# Interconnect_board_v1p10.net
KiCad netlist of a schematic drawn in EAGLE
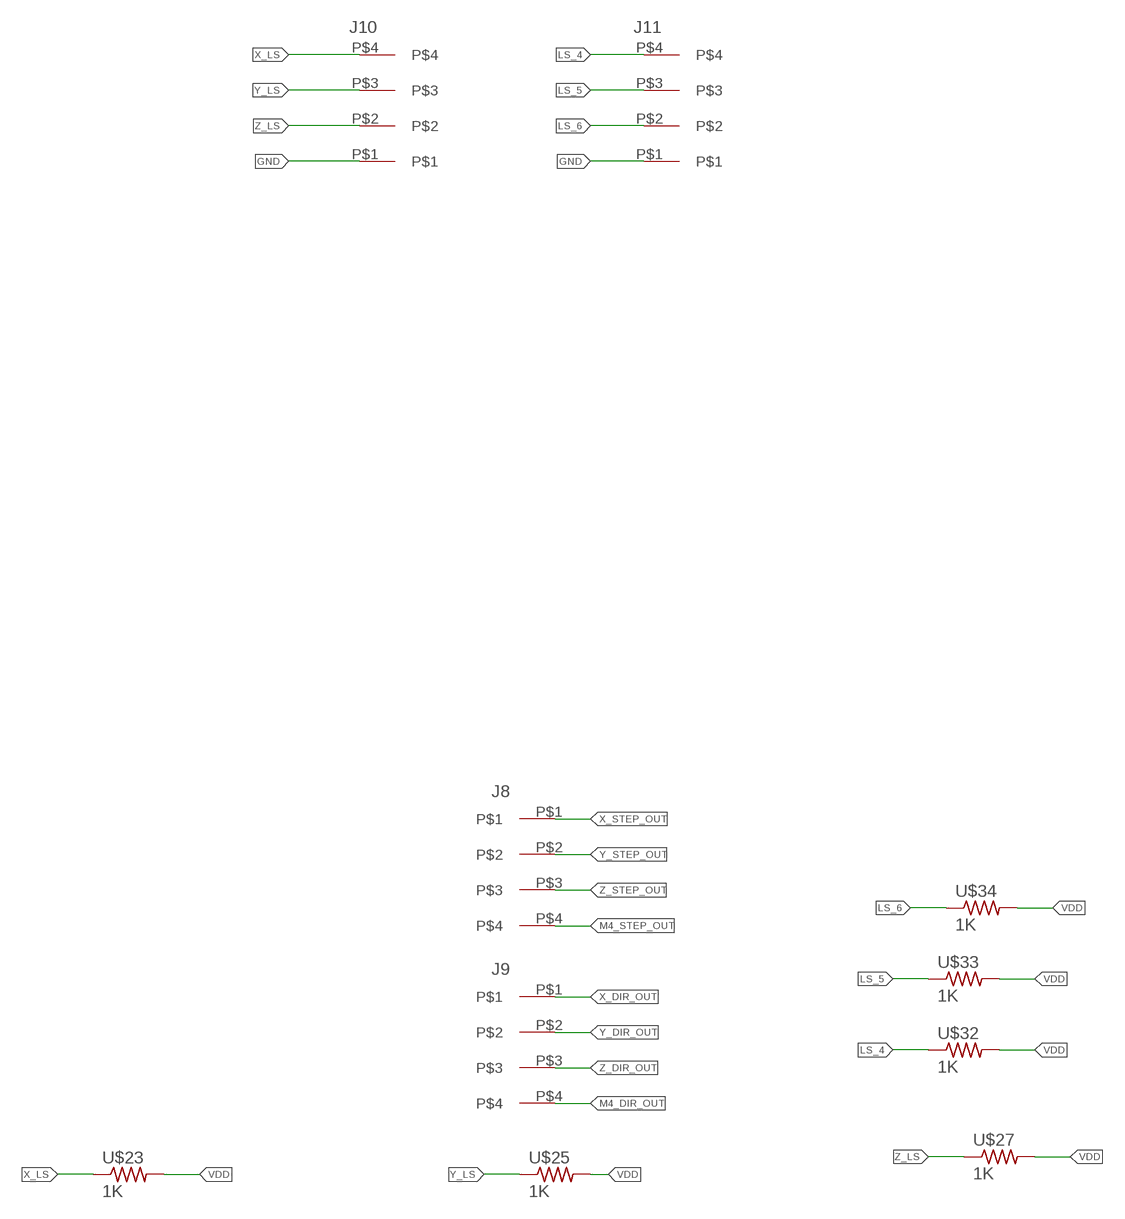
[diagram p0: schematic, sheet 1, part 1 of 2]
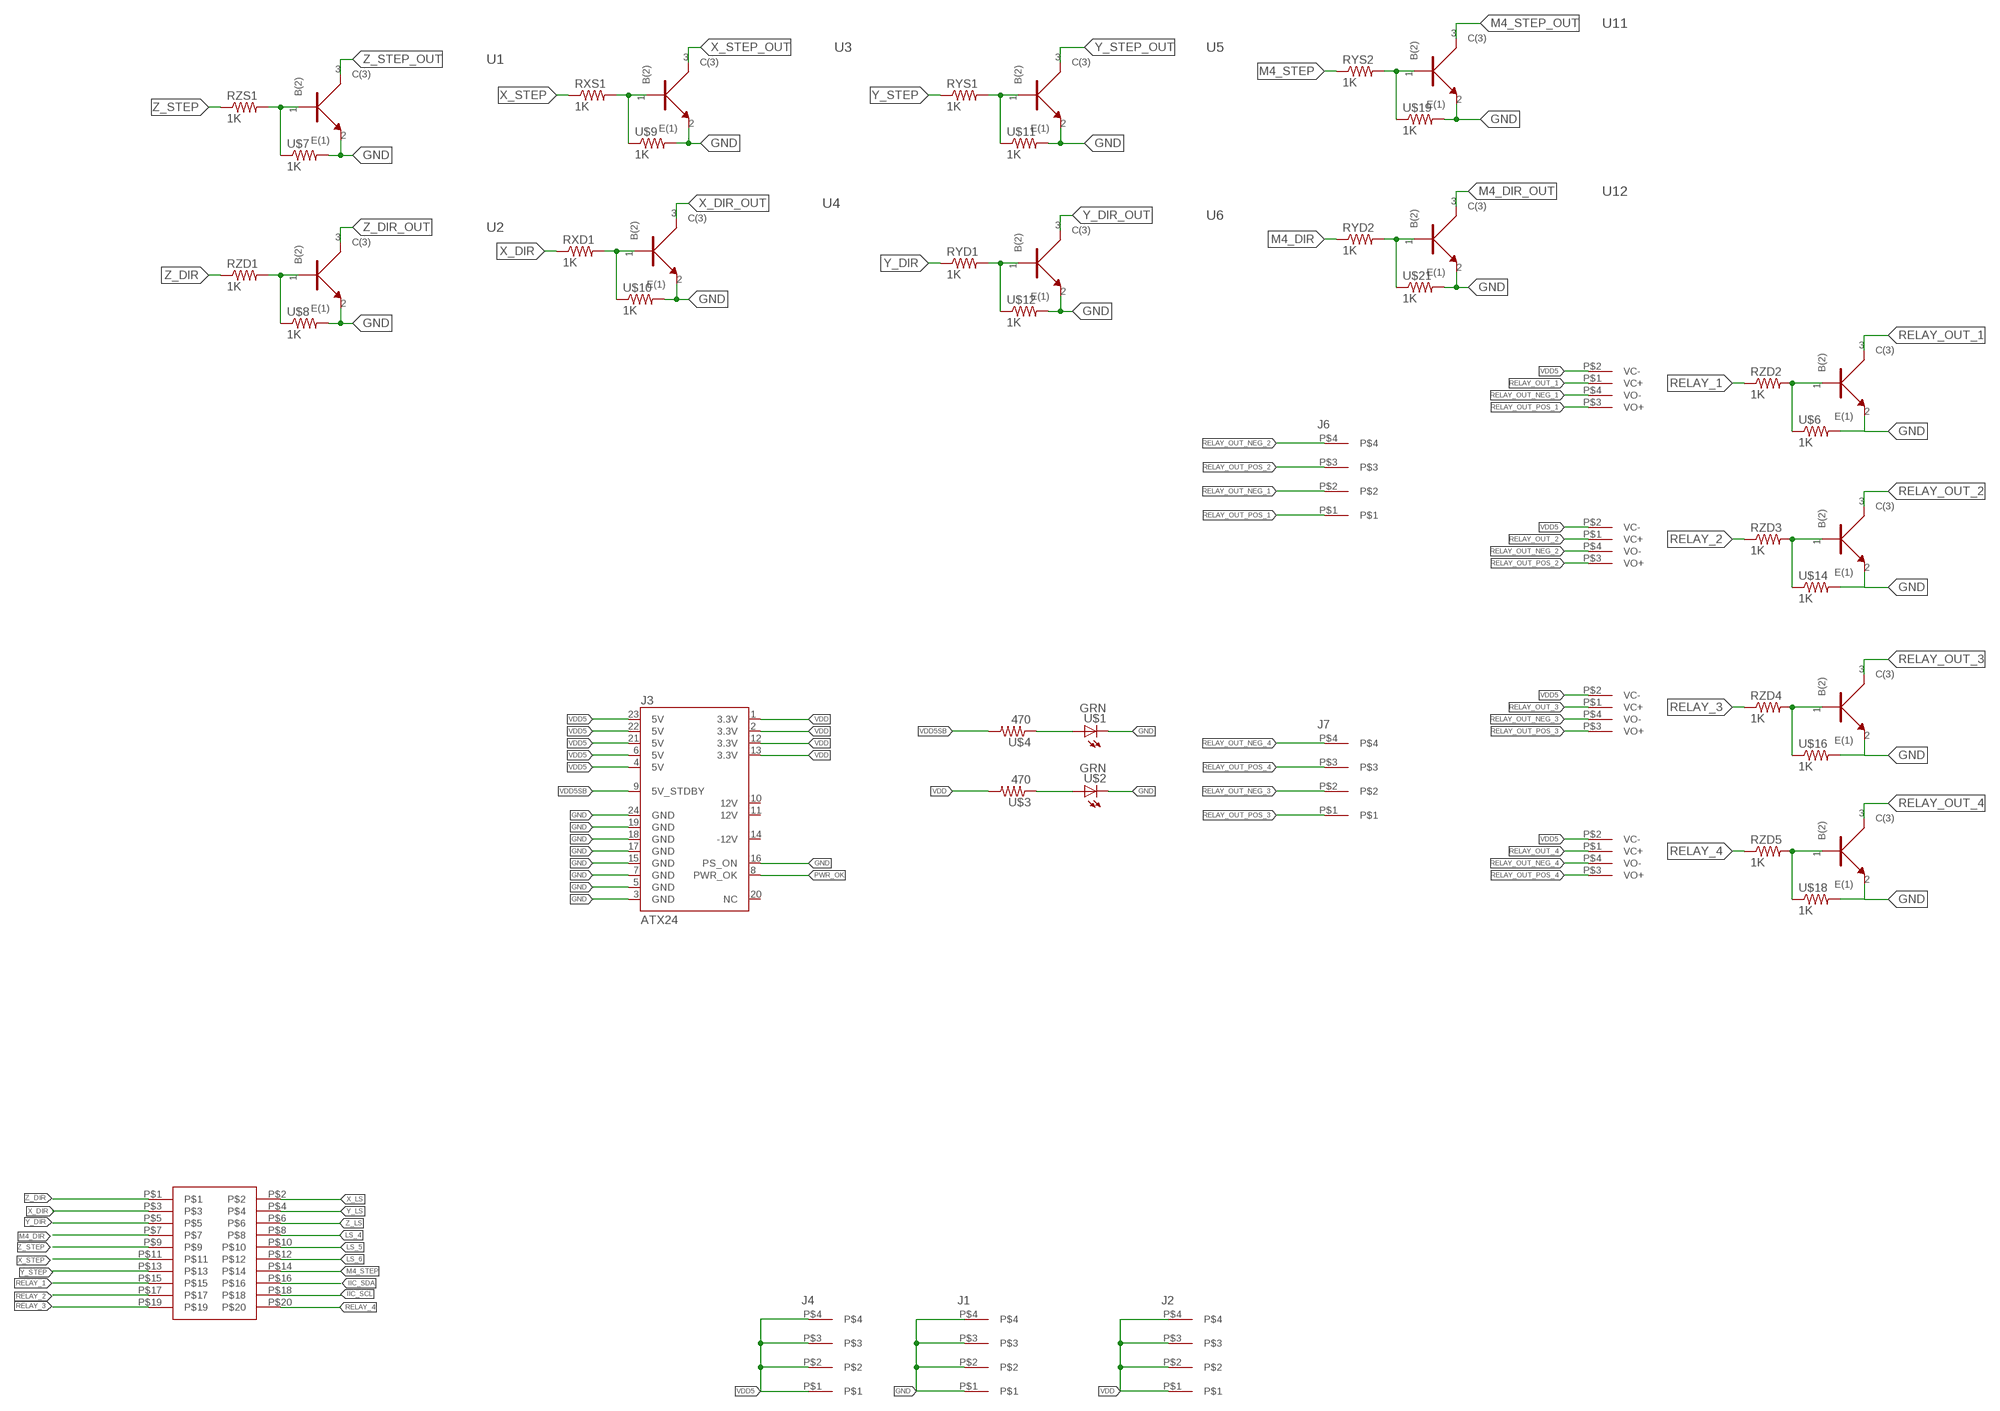
[diagram p1: schematic, sheet 1, part 2 of 2]

(export (version "E")
  (design (tool "Eeschema 10.0.6"))
  (components
    (comp (ref "J1")
      (value "3.81MM_1_X_4_RT_ANGLE_PLUG_HEADER")
      (footprint "eagle-import:1X4_3.81MM_PITCH")
      (libsource (lib "eagle-import") (part "3.81MM_1_X_4_RT_ANGLE_PLUG_HEADER"))
    )
    (comp (ref "J2")
      (value "3.81MM_1_X_4_RT_ANGLE_PLUG_HEADER")
      (footprint "eagle-import:1X4_3.81MM_PITCH")
      (libsource (lib "eagle-import") (part "3.81MM_1_X_4_RT_ANGLE_PLUG_HEADER"))
    )
    (comp (ref "J3")
      (value "ATX24")
      (footprint "eagle-import:ATX24_STRAIGHT")
      (libsource (lib "eagle-import") (part "ATX24"))
    )
    (comp (ref "J4")
      (value "3.81MM_1_X_4_RT_ANGLE_PLUG_HEADER")
      (footprint "eagle-import:1X4_3.81MM_PITCH")
      (libsource (lib "eagle-import") (part "3.81MM_1_X_4_RT_ANGLE_PLUG_HEADER"))
    )
    (comp (ref "J6")
      (value "3.81MM_1_X_4_RT_ANGLE_PLUG_HEADER")
      (footprint "eagle-import:1X4_3.81MM_PITCH")
      (libsource (lib "eagle-import") (part "3.81MM_1_X_4_RT_ANGLE_PLUG_HEADER"))
    )
    (comp (ref "J7")
      (value "3.81MM_1_X_4_RT_ANGLE_PLUG_HEADER")
      (footprint "eagle-import:1X4_3.81MM_PITCH")
      (libsource (lib "eagle-import") (part "3.81MM_1_X_4_RT_ANGLE_PLUG_HEADER"))
    )
    (comp (ref "J8")
      (value "3.81MM_1_X_4_RT_ANGLE_PLUG_HEADER")
      (footprint "eagle-import:1X4_3.81MM_PITCH")
      (libsource (lib "eagle-import") (part "3.81MM_1_X_4_RT_ANGLE_PLUG_HEADER"))
    )
    (comp (ref "J9")
      (value "3.81MM_1_X_4_RT_ANGLE_PLUG_HEADER")
      (footprint "eagle-import:1X4_3.81MM_PITCH")
      (libsource (lib "eagle-import") (part "3.81MM_1_X_4_RT_ANGLE_PLUG_HEADER"))
    )
    (comp (ref "J10")
      (value "3.81MM_1_X_4_RT_ANGLE_PLUG_HEADER")
      (footprint "eagle-import:1X4_3.81MM_PITCH")
      (libsource (lib "eagle-import") (part "3.81MM_1_X_4_RT_ANGLE_PLUG_HEADER"))
    )
    (comp (ref "J11")
      (value "3.81MM_1_X_4_RT_ANGLE_PLUG_HEADER")
      (footprint "eagle-import:1X4_3.81MM_PITCH")
      (libsource (lib "eagle-import") (part "3.81MM_1_X_4_RT_ANGLE_PLUG_HEADER"))
    )
    (comp (ref "RXD1")
      (value "R_0805_1K")
      (footprint "eagle-import:R_0805_1K")
      (libsource (lib "eagle-import") (part "R_0805_1K"))
    )
    (comp (ref "RXS1")
      (value "R_0805_1K")
      (footprint "eagle-import:R_0805_1K")
      (libsource (lib "eagle-import") (part "R_0805_1K"))
    )
    (comp (ref "RYD1")
      (value "R_0805_1K")
      (footprint "eagle-import:R_0805_1K")
      (libsource (lib "eagle-import") (part "R_0805_1K"))
    )
    (comp (ref "RYD2")
      (value "R_0805_1K")
      (footprint "eagle-import:R_0805_1K")
      (libsource (lib "eagle-import") (part "R_0805_1K"))
    )
    (comp (ref "RYS1")
      (value "R_0805_1K")
      (footprint "eagle-import:R_0805_1K")
      (libsource (lib "eagle-import") (part "R_0805_1K"))
    )
    (comp (ref "RYS2")
      (value "R_0805_1K")
      (footprint "eagle-import:R_0805_1K")
      (libsource (lib "eagle-import") (part "R_0805_1K"))
    )
    (comp (ref "RZD1")
      (value "R_0805_1K")
      (footprint "eagle-import:R_0805_1K")
      (libsource (lib "eagle-import") (part "R_0805_1K"))
    )
    (comp (ref "RZD2")
      (value "R_0805_1K")
      (footprint "eagle-import:R_0805_1K")
      (libsource (lib "eagle-import") (part "R_0805_1K"))
    )
    (comp (ref "RZD3")
      (value "R_0805_1K")
      (footprint "eagle-import:R_0805_1K")
      (libsource (lib "eagle-import") (part "R_0805_1K"))
    )
    (comp (ref "RZD4")
      (value "R_0805_1K")
      (footprint "eagle-import:R_0805_1K")
      (libsource (lib "eagle-import") (part "R_0805_1K"))
    )
    (comp (ref "RZD5")
      (value "R_0805_1K")
      (footprint "eagle-import:R_0805_1K")
      (libsource (lib "eagle-import") (part "R_0805_1K"))
    )
    (comp (ref "RZS1")
      (value "R_0805_1K")
      (footprint "eagle-import:R_0805_1K")
      (libsource (lib "eagle-import") (part "R_0805_1K"))
    )
    (comp (ref "U$1")
      (value "LED_0805_GREEN")
      (footprint "eagle-import:LED_0805_GREEN")
      (libsource (lib "eagle-import") (part "LED_0805_GREEN"))
    )
    (comp (ref "U$2")
      (value "LED_0805_GREEN")
      (footprint "eagle-import:LED_0805_GREEN")
      (libsource (lib "eagle-import") (part "LED_0805_GREEN"))
    )
    (comp (ref "U$3")
      (value "R_0805_470")
      (footprint "eagle-import:R_0805_470")
      (libsource (lib "eagle-import") (part "R_0805_470"))
    )
    (comp (ref "U$4")
      (value "R_0805_470")
      (footprint "eagle-import:R_0805_470")
      (libsource (lib "eagle-import") (part "R_0805_470"))
    )
    (comp (ref "U$5")
      (value "RELAY_KYOTO_KF0604D")
      (footprint "eagle-import:RELAY_KYOTO_KF0604D")
      (libsource (lib "eagle-import") (part "RELAY_KYOTO_KF0604D"))
    )
    (comp (ref "U$6")
      (value "R_0805_1K")
      (footprint "eagle-import:R_0805_1K")
      (libsource (lib "eagle-import") (part "R_0805_1K"))
    )
    (comp (ref "U$7")
      (value "R_0805_1K")
      (footprint "eagle-import:R_0805_1K")
      (libsource (lib "eagle-import") (part "R_0805_1K"))
    )
    (comp (ref "U$8")
      (value "R_0805_1K")
      (footprint "eagle-import:R_0805_1K")
      (libsource (lib "eagle-import") (part "R_0805_1K"))
    )
    (comp (ref "U$9")
      (value "R_0805_1K")
      (footprint "eagle-import:R_0805_1K")
      (libsource (lib "eagle-import") (part "R_0805_1K"))
    )
    (comp (ref "U$10")
      (value "R_0805_1K")
      (footprint "eagle-import:R_0805_1K")
      (libsource (lib "eagle-import") (part "R_0805_1K"))
    )
    (comp (ref "U$11")
      (value "R_0805_1K")
      (footprint "eagle-import:R_0805_1K")
      (libsource (lib "eagle-import") (part "R_0805_1K"))
    )
    (comp (ref "U$12")
      (value "R_0805_1K")
      (footprint "eagle-import:R_0805_1K")
      (libsource (lib "eagle-import") (part "R_0805_1K"))
    )
    (comp (ref "U$13")
      (value "RELAY_KYOTO_KF0604D")
      (footprint "eagle-import:RELAY_KYOTO_KF0604D")
      (libsource (lib "eagle-import") (part "RELAY_KYOTO_KF0604D"))
    )
    (comp (ref "U$14")
      (value "R_0805_1K")
      (footprint "eagle-import:R_0805_1K")
      (libsource (lib "eagle-import") (part "R_0805_1K"))
    )
    (comp (ref "U$15")
      (value "RELAY_KYOTO_KF0604D")
      (footprint "eagle-import:RELAY_KYOTO_KF0604D")
      (libsource (lib "eagle-import") (part "RELAY_KYOTO_KF0604D"))
    )
    (comp (ref "U$16")
      (value "R_0805_1K")
      (footprint "eagle-import:R_0805_1K")
      (libsource (lib "eagle-import") (part "R_0805_1K"))
    )
    (comp (ref "U$17")
      (value "RELAY_KYOTO_KF0604D")
      (footprint "eagle-import:RELAY_KYOTO_KF0604D")
      (libsource (lib "eagle-import") (part "RELAY_KYOTO_KF0604D"))
    )
    (comp (ref "U$18")
      (value "R_0805_1K")
      (footprint "eagle-import:R_0805_1K")
      (libsource (lib "eagle-import") (part "R_0805_1K"))
    )
    (comp (ref "U$19")
      (value "R_0805_1K")
      (footprint "eagle-import:R_0805_1K")
      (libsource (lib "eagle-import") (part "R_0805_1K"))
    )
    (comp (ref "U$21")
      (value "R_0805_1K")
      (footprint "eagle-import:R_0805_1K")
      (libsource (lib "eagle-import") (part "R_0805_1K"))
    )
    (comp (ref "U$23")
      (value "R_0805_1K")
      (footprint "eagle-import:R_0805_1K")
      (libsource (lib "eagle-import") (part "R_0805_1K"))
    )
    (comp (ref "U$25")
      (value "R_0805_1K")
      (footprint "eagle-import:R_0805_1K")
      (libsource (lib "eagle-import") (part "R_0805_1K"))
    )
    (comp (ref "U$26")
      (value "2_X_10_HEADER_GENERIC")
      (footprint "eagle-import:2_X_10_.1_INCH")
      (libsource (lib "eagle-import") (part "2_X_10_HEADER_GENERIC"))
    )
    (comp (ref "U$27")
      (value "R_0805_1K")
      (footprint "eagle-import:R_0805_1K")
      (libsource (lib "eagle-import") (part "R_0805_1K"))
    )
    (comp (ref "U$32")
      (value "R_0805_1K")
      (footprint "eagle-import:R_0805_1K")
      (libsource (lib "eagle-import") (part "R_0805_1K"))
    )
    (comp (ref "U$33")
      (value "R_0805_1K")
      (footprint "eagle-import:R_0805_1K")
      (libsource (lib "eagle-import") (part "R_0805_1K"))
    )
    (comp (ref "U$34")
      (value "R_0805_1K")
      (footprint "eagle-import:R_0805_1K")
      (libsource (lib "eagle-import") (part "R_0805_1K"))
    )
    (comp (ref "U1")
      (value "BC846BW")
      (footprint "eagle-import:SOT323")
      (libsource (lib "eagle-import") (part "BC846BW"))
    )
    (comp (ref "U2")
      (value "BC846BW")
      (footprint "eagle-import:SOT323")
      (libsource (lib "eagle-import") (part "BC846BW"))
    )
    (comp (ref "U3")
      (value "BC846BW")
      (footprint "eagle-import:SOT323")
      (libsource (lib "eagle-import") (part "BC846BW"))
    )
    (comp (ref "U4")
      (value "BC846BW")
      (footprint "eagle-import:SOT323")
      (libsource (lib "eagle-import") (part "BC846BW"))
    )
    (comp (ref "U5")
      (value "BC846BW")
      (footprint "eagle-import:SOT323")
      (libsource (lib "eagle-import") (part "BC846BW"))
    )
    (comp (ref "U6")
      (value "BC846BW")
      (footprint "eagle-import:SOT323")
      (libsource (lib "eagle-import") (part "BC846BW"))
    )
    (comp (ref "U7")
      (value "BC846BW")
      (footprint "eagle-import:SOT323")
      (libsource (lib "eagle-import") (part "BC846BW"))
    )
    (comp (ref "U8")
      (value "BC846BW")
      (footprint "eagle-import:SOT323")
      (libsource (lib "eagle-import") (part "BC846BW"))
    )
    (comp (ref "U9")
      (value "BC846BW")
      (footprint "eagle-import:SOT323")
      (libsource (lib "eagle-import") (part "BC846BW"))
    )
    (comp (ref "U10")
      (value "BC846BW")
      (footprint "eagle-import:SOT323")
      (libsource (lib "eagle-import") (part "BC846BW"))
    )
    (comp (ref "U11")
      (value "BC846BW")
      (footprint "eagle-import:SOT323")
      (libsource (lib "eagle-import") (part "BC846BW"))
    )
    (comp (ref "U12")
      (value "BC846BW")
      (footprint "eagle-import:SOT323")
      (libsource (lib "eagle-import") (part "BC846BW"))
    )
  )
  (nets
    (net (code "1") (name "GND") (class "Default")
      (node (ref "J1") (pin "P$1") (pinfunction "P$1_P$1") (pintype "bidirectional"))
      (node (ref "J1") (pin "P$2") (pinfunction "P$2_P$2") (pintype "bidirectional"))
      (node (ref "J1") (pin "P$3") (pinfunction "P$3_P$3") (pintype "bidirectional"))
      (node (ref "J1") (pin "P$4") (pinfunction "P$4_P$4") (pintype "bidirectional"))
      (node (ref "J10") (pin "P$1") (pinfunction "P$1_P$1") (pintype "bidirectional"))
      (node (ref "J11") (pin "P$1") (pinfunction "P$1_P$1") (pintype "bidirectional"))
      (node (ref "J3") (pin "15") (pinfunction "GND_15") (pintype "bidirectional"))
      (node (ref "J3") (pin "16") (pinfunction "PS_ON_16") (pintype "bidirectional"))
      (node (ref "J3") (pin "17") (pinfunction "GND_17") (pintype "bidirectional"))
      (node (ref "J3") (pin "18") (pinfunction "GND_18") (pintype "bidirectional"))
      (node (ref "J3") (pin "19") (pinfunction "GND_19") (pintype "bidirectional"))
      (node (ref "J3") (pin "24") (pinfunction "GND_24") (pintype "bidirectional"))
      (node (ref "J3") (pin "3") (pinfunction "GND_3") (pintype "bidirectional"))
      (node (ref "J3") (pin "5") (pinfunction "GND_5") (pintype "bidirectional"))
      (node (ref "J3") (pin "7") (pinfunction "GND_7") (pintype "bidirectional"))
      (node (ref "U$1") (pin "C") (pinfunction "C_C") (pintype "passive"))
      (node (ref "U$10") (pin "2") (pinfunction "2_2") (pintype "passive"))
      (node (ref "U$11") (pin "2") (pinfunction "2_2") (pintype "passive"))
      (node (ref "U$12") (pin "2") (pinfunction "2_2") (pintype "passive"))
      (node (ref "U$14") (pin "2") (pinfunction "2_2") (pintype "passive"))
      (node (ref "U$16") (pin "2") (pinfunction "2_2") (pintype "passive"))
      (node (ref "U$18") (pin "2") (pinfunction "2_2") (pintype "passive"))
      (node (ref "U$19") (pin "2") (pinfunction "2_2") (pintype "passive"))
      (node (ref "U$2") (pin "C") (pinfunction "C_C") (pintype "passive"))
      (node (ref "U$21") (pin "2") (pinfunction "2_2") (pintype "passive"))
      (node (ref "U$6") (pin "2") (pinfunction "2_2") (pintype "passive"))
      (node (ref "U$7") (pin "2") (pinfunction "2_2") (pintype "passive"))
      (node (ref "U$8") (pin "2") (pinfunction "2_2") (pintype "passive"))
      (node (ref "U$9") (pin "2") (pinfunction "2_2") (pintype "passive"))
      (node (ref "U1") (pin "2") (pinfunction "E(1)_2") (pintype "output"))
      (node (ref "U10") (pin "2") (pinfunction "E(1)_2") (pintype "output"))
      (node (ref "U11") (pin "2") (pinfunction "E(1)_2") (pintype "output"))
      (node (ref "U12") (pin "2") (pinfunction "E(1)_2") (pintype "output"))
      (node (ref "U2") (pin "2") (pinfunction "E(1)_2") (pintype "output"))
      (node (ref "U3") (pin "2") (pinfunction "E(1)_2") (pintype "output"))
      (node (ref "U4") (pin "2") (pinfunction "E(1)_2") (pintype "output"))
      (node (ref "U5") (pin "2") (pinfunction "E(1)_2") (pintype "output"))
      (node (ref "U6") (pin "2") (pinfunction "E(1)_2") (pintype "output"))
      (node (ref "U7") (pin "2") (pinfunction "E(1)_2") (pintype "output"))
      (node (ref "U8") (pin "2") (pinfunction "E(1)_2") (pintype "output"))
      (node (ref "U9") (pin "2") (pinfunction "E(1)_2") (pintype "output"))
    )
    (net (code "2") (name "IIC_SCL") (class "Default")
      (node (ref "U$26") (pin "P$18") (pinfunction "P$18_P$18") (pintype "bidirectional"))
    )
    (net (code "3") (name "IIC_SDA") (class "Default")
      (node (ref "U$26") (pin "P$16") (pinfunction "P$16_P$16") (pintype "bidirectional"))
    )
    (net (code "4") (name "LS_4") (class "Default")
      (node (ref "J11") (pin "P$4") (pinfunction "P$4_P$4") (pintype "bidirectional"))
      (node (ref "U$26") (pin "P$8") (pinfunction "P$8_P$8") (pintype "bidirectional"))
      (node (ref "U$32") (pin "1") (pinfunction "1_1") (pintype "passive"))
    )
    (net (code "5") (name "LS_5") (class "Default")
      (node (ref "J11") (pin "P$3") (pinfunction "P$3_P$3") (pintype "bidirectional"))
      (node (ref "U$26") (pin "P$10") (pinfunction "P$10_P$10") (pintype "bidirectional"))
      (node (ref "U$33") (pin "1") (pinfunction "1_1") (pintype "passive"))
    )
    (net (code "6") (name "LS_6") (class "Default")
      (node (ref "J11") (pin "P$2") (pinfunction "P$2_P$2") (pintype "bidirectional"))
      (node (ref "U$26") (pin "P$12") (pinfunction "P$12_P$12") (pintype "bidirectional"))
      (node (ref "U$34") (pin "1") (pinfunction "1_1") (pintype "passive"))
    )
    (net (code "7") (name "M4_DIR") (class "Default")
      (node (ref "RYD2") (pin "1") (pinfunction "1_1") (pintype "passive"))
      (node (ref "U$26") (pin "P$7") (pinfunction "P$7_P$7") (pintype "bidirectional"))
    )
    (net (code "8") (name "M4_DIR_OUT") (class "Default")
      (node (ref "J9") (pin "P$4") (pinfunction "P$4_P$4") (pintype "bidirectional"))
      (node (ref "U12") (pin "3") (pinfunction "C(3)_3") (pintype "input"))
    )
    (net (code "9") (name "M4_STEP") (class "Default")
      (node (ref "RYS2") (pin "1") (pinfunction "1_1") (pintype "passive"))
      (node (ref "U$26") (pin "P$14") (pinfunction "P$14_P$14") (pintype "bidirectional"))
    )
    (net (code "10") (name "M4_STEP_OUT") (class "Default")
      (node (ref "J8") (pin "P$4") (pinfunction "P$4_P$4") (pintype "bidirectional"))
      (node (ref "U11") (pin "3") (pinfunction "C(3)_3") (pintype "input"))
    )
    (net (code "11") (name "Net-(U$1-PadA)") (class "Default")
      (node (ref "U$1") (pin "A") (pinfunction "A_A") (pintype "passive"))
      (node (ref "U$4") (pin "1") (pinfunction "1_1") (pintype "passive"))
    )
    (net (code "12") (name "Net-(U$2-PadA)") (class "Default")
      (node (ref "U$2") (pin "A") (pinfunction "A_A") (pintype "passive"))
      (node (ref "U$3") (pin "1") (pinfunction "1_1") (pintype "passive"))
    )
    (net (code "13") (name "Net-(U1-B(2))") (class "Default")
      (node (ref "RZS1") (pin "2") (pinfunction "2_2") (pintype "passive"))
      (node (ref "U$7") (pin "1") (pinfunction "1_1") (pintype "passive"))
      (node (ref "U1") (pin "1") (pinfunction "B(2)_1") (pintype "input"))
    )
    (net (code "14") (name "Net-(U2-B(2))") (class "Default")
      (node (ref "RZD1") (pin "2") (pinfunction "2_2") (pintype "passive"))
      (node (ref "U$8") (pin "1") (pinfunction "1_1") (pintype "passive"))
      (node (ref "U2") (pin "1") (pinfunction "B(2)_1") (pintype "input"))
    )
    (net (code "15") (name "Net-(U3-B(2))") (class "Default")
      (node (ref "RXS1") (pin "2") (pinfunction "2_2") (pintype "passive"))
      (node (ref "U$9") (pin "1") (pinfunction "1_1") (pintype "passive"))
      (node (ref "U3") (pin "1") (pinfunction "B(2)_1") (pintype "input"))
    )
    (net (code "16") (name "Net-(U4-B(2))") (class "Default")
      (node (ref "RXD1") (pin "2") (pinfunction "2_2") (pintype "passive"))
      (node (ref "U$10") (pin "1") (pinfunction "1_1") (pintype "passive"))
      (node (ref "U4") (pin "1") (pinfunction "B(2)_1") (pintype "input"))
    )
    (net (code "17") (name "Net-(U5-B(2))") (class "Default")
      (node (ref "RYS1") (pin "2") (pinfunction "2_2") (pintype "passive"))
      (node (ref "U$11") (pin "1") (pinfunction "1_1") (pintype "passive"))
      (node (ref "U5") (pin "1") (pinfunction "B(2)_1") (pintype "input"))
    )
    (net (code "18") (name "Net-(U6-B(2))") (class "Default")
      (node (ref "RYD1") (pin "2") (pinfunction "2_2") (pintype "passive"))
      (node (ref "U$12") (pin "1") (pinfunction "1_1") (pintype "passive"))
      (node (ref "U6") (pin "1") (pinfunction "B(2)_1") (pintype "input"))
    )
    (net (code "19") (name "Net-(U7-B(2))") (class "Default")
      (node (ref "RZD2") (pin "2") (pinfunction "2_2") (pintype "passive"))
      (node (ref "U$6") (pin "1") (pinfunction "1_1") (pintype "passive"))
      (node (ref "U7") (pin "1") (pinfunction "B(2)_1") (pintype "input"))
    )
    (net (code "20") (name "Net-(U8-B(2))") (class "Default")
      (node (ref "RZD3") (pin "2") (pinfunction "2_2") (pintype "passive"))
      (node (ref "U$14") (pin "1") (pinfunction "1_1") (pintype "passive"))
      (node (ref "U8") (pin "1") (pinfunction "B(2)_1") (pintype "input"))
    )
    (net (code "21") (name "Net-(U9-B(2))") (class "Default")
      (node (ref "RZD4") (pin "2") (pinfunction "2_2") (pintype "passive"))
      (node (ref "U$16") (pin "1") (pinfunction "1_1") (pintype "passive"))
      (node (ref "U9") (pin "1") (pinfunction "B(2)_1") (pintype "input"))
    )
    (net (code "22") (name "Net-(U10-B(2))") (class "Default")
      (node (ref "RZD5") (pin "2") (pinfunction "2_2") (pintype "passive"))
      (node (ref "U$18") (pin "1") (pinfunction "1_1") (pintype "passive"))
      (node (ref "U10") (pin "1") (pinfunction "B(2)_1") (pintype "input"))
    )
    (net (code "23") (name "Net-(U11-B(2))") (class "Default")
      (node (ref "RYS2") (pin "2") (pinfunction "2_2") (pintype "passive"))
      (node (ref "U$19") (pin "1") (pinfunction "1_1") (pintype "passive"))
      (node (ref "U11") (pin "1") (pinfunction "B(2)_1") (pintype "input"))
    )
    (net (code "24") (name "Net-(U12-B(2))") (class "Default")
      (node (ref "RYD2") (pin "2") (pinfunction "2_2") (pintype "passive"))
      (node (ref "U$21") (pin "1") (pinfunction "1_1") (pintype "passive"))
      (node (ref "U12") (pin "1") (pinfunction "B(2)_1") (pintype "input"))
    )
    (net (code "25") (name "PWR_OK") (class "Default")
      (node (ref "J3") (pin "8") (pinfunction "PWR_OK_8") (pintype "bidirectional"))
    )
    (net (code "26") (name "RELAY_1") (class "Default")
      (node (ref "RZD2") (pin "1") (pinfunction "1_1") (pintype "passive"))
      (node (ref "U$26") (pin "P$15") (pinfunction "P$15_P$15") (pintype "bidirectional"))
    )
    (net (code "27") (name "RELAY_2") (class "Default")
      (node (ref "RZD3") (pin "1") (pinfunction "1_1") (pintype "passive"))
      (node (ref "U$26") (pin "P$17") (pinfunction "P$17_P$17") (pintype "bidirectional"))
    )
    (net (code "28") (name "RELAY_3") (class "Default")
      (node (ref "RZD4") (pin "1") (pinfunction "1_1") (pintype "passive"))
      (node (ref "U$26") (pin "P$19") (pinfunction "P$19_P$19") (pintype "bidirectional"))
    )
    (net (code "29") (name "RELAY_4") (class "Default")
      (node (ref "RZD5") (pin "1") (pinfunction "1_1") (pintype "passive"))
      (node (ref "U$26") (pin "P$20") (pinfunction "P$20_P$20") (pintype "bidirectional"))
    )
    (net (code "30") (name "RELAY_OUT_1") (class "Default")
      (node (ref "U$5") (pin "P$1") (pinfunction "VC+_P$1") (pintype "bidirectional"))
      (node (ref "U7") (pin "3") (pinfunction "C(3)_3") (pintype "input"))
    )
    (net (code "31") (name "RELAY_OUT_2") (class "Default")
      (node (ref "U$13") (pin "P$1") (pinfunction "VC+_P$1") (pintype "bidirectional"))
      (node (ref "U8") (pin "3") (pinfunction "C(3)_3") (pintype "input"))
    )
    (net (code "32") (name "RELAY_OUT_3") (class "Default")
      (node (ref "U$15") (pin "P$1") (pinfunction "VC+_P$1") (pintype "bidirectional"))
      (node (ref "U9") (pin "3") (pinfunction "C(3)_3") (pintype "input"))
    )
    (net (code "33") (name "RELAY_OUT_4") (class "Default")
      (node (ref "U$17") (pin "P$1") (pinfunction "VC+_P$1") (pintype "bidirectional"))
      (node (ref "U10") (pin "3") (pinfunction "C(3)_3") (pintype "input"))
    )
    (net (code "34") (name "RELAY_OUT_NEG_1") (class "Default")
      (node (ref "J6") (pin "P$2") (pinfunction "P$2_P$2") (pintype "bidirectional"))
      (node (ref "U$5") (pin "P$4") (pinfunction "VO-_P$4") (pintype "bidirectional"))
    )
    (net (code "35") (name "RELAY_OUT_NEG_2") (class "Default")
      (node (ref "J6") (pin "P$4") (pinfunction "P$4_P$4") (pintype "bidirectional"))
      (node (ref "U$13") (pin "P$4") (pinfunction "VO-_P$4") (pintype "bidirectional"))
    )
    (net (code "36") (name "RELAY_OUT_NEG_3") (class "Default")
      (node (ref "J7") (pin "P$2") (pinfunction "P$2_P$2") (pintype "bidirectional"))
      (node (ref "U$15") (pin "P$4") (pinfunction "VO-_P$4") (pintype "bidirectional"))
    )
    (net (code "37") (name "RELAY_OUT_NEG_4") (class "Default")
      (node (ref "J7") (pin "P$4") (pinfunction "P$4_P$4") (pintype "bidirectional"))
      (node (ref "U$17") (pin "P$4") (pinfunction "VO-_P$4") (pintype "bidirectional"))
    )
    (net (code "38") (name "RELAY_OUT_POS_1") (class "Default")
      (node (ref "J6") (pin "P$1") (pinfunction "P$1_P$1") (pintype "bidirectional"))
      (node (ref "U$5") (pin "P$3") (pinfunction "VO+_P$3") (pintype "bidirectional"))
    )
    (net (code "39") (name "RELAY_OUT_POS_2") (class "Default")
      (node (ref "J6") (pin "P$3") (pinfunction "P$3_P$3") (pintype "bidirectional"))
      (node (ref "U$13") (pin "P$3") (pinfunction "VO+_P$3") (pintype "bidirectional"))
    )
    (net (code "40") (name "RELAY_OUT_POS_3") (class "Default")
      (node (ref "J7") (pin "P$1") (pinfunction "P$1_P$1") (pintype "bidirectional"))
      (node (ref "U$15") (pin "P$3") (pinfunction "VO+_P$3") (pintype "bidirectional"))
    )
    (net (code "41") (name "RELAY_OUT_POS_4") (class "Default")
      (node (ref "J7") (pin "P$3") (pinfunction "P$3_P$3") (pintype "bidirectional"))
      (node (ref "U$17") (pin "P$3") (pinfunction "VO+_P$3") (pintype "bidirectional"))
    )
    (net (code "42") (name "VDD") (class "Default")
      (node (ref "J2") (pin "P$1") (pinfunction "P$1_P$1") (pintype "bidirectional"))
      (node (ref "J2") (pin "P$2") (pinfunction "P$2_P$2") (pintype "bidirectional"))
      (node (ref "J2") (pin "P$3") (pinfunction "P$3_P$3") (pintype "bidirectional"))
      (node (ref "J2") (pin "P$4") (pinfunction "P$4_P$4") (pintype "bidirectional"))
      (node (ref "J3") (pin "1") (pinfunction "3.3V_1") (pintype "bidirectional"))
      (node (ref "J3") (pin "12") (pinfunction "3.3V_12") (pintype "bidirectional"))
      (node (ref "J3") (pin "13") (pinfunction "3.3V_13") (pintype "bidirectional"))
      (node (ref "J3") (pin "2") (pinfunction "3.3V_2") (pintype "bidirectional"))
      (node (ref "U$23") (pin "2") (pinfunction "2_2") (pintype "passive"))
      (node (ref "U$25") (pin "2") (pinfunction "2_2") (pintype "passive"))
      (node (ref "U$27") (pin "2") (pinfunction "2_2") (pintype "passive"))
      (node (ref "U$3") (pin "2") (pinfunction "2_2") (pintype "passive"))
      (node (ref "U$32") (pin "2") (pinfunction "2_2") (pintype "passive"))
      (node (ref "U$33") (pin "2") (pinfunction "2_2") (pintype "passive"))
      (node (ref "U$34") (pin "2") (pinfunction "2_2") (pintype "passive"))
    )
    (net (code "43") (name "VDD5") (class "Default")
      (node (ref "J3") (pin "21") (pinfunction "5V_21") (pintype "bidirectional"))
      (node (ref "J3") (pin "22") (pinfunction "5V_22") (pintype "bidirectional"))
      (node (ref "J3") (pin "23") (pinfunction "5V_23") (pintype "bidirectional"))
      (node (ref "J3") (pin "4") (pinfunction "5V_4") (pintype "bidirectional"))
      (node (ref "J3") (pin "6") (pinfunction "5V_6") (pintype "bidirectional"))
      (node (ref "J4") (pin "P$1") (pinfunction "P$1_P$1") (pintype "bidirectional"))
      (node (ref "J4") (pin "P$2") (pinfunction "P$2_P$2") (pintype "bidirectional"))
      (node (ref "J4") (pin "P$3") (pinfunction "P$3_P$3") (pintype "bidirectional"))
      (node (ref "J4") (pin "P$4") (pinfunction "P$4_P$4") (pintype "bidirectional"))
      (node (ref "U$13") (pin "P$2") (pinfunction "VC-_P$2") (pintype "bidirectional"))
      (node (ref "U$15") (pin "P$2") (pinfunction "VC-_P$2") (pintype "bidirectional"))
      (node (ref "U$17") (pin "P$2") (pinfunction "VC-_P$2") (pintype "bidirectional"))
      (node (ref "U$5") (pin "P$2") (pinfunction "VC-_P$2") (pintype "bidirectional"))
    )
    (net (code "44") (name "VDD5SB") (class "Default")
      (node (ref "J3") (pin "9") (pinfunction "5V_STDBY_9") (pintype "bidirectional"))
      (node (ref "U$4") (pin "2") (pinfunction "2_2") (pintype "passive"))
    )
    (net (code "45") (name "X_DIR") (class "Default")
      (node (ref "RXD1") (pin "1") (pinfunction "1_1") (pintype "passive"))
      (node (ref "U$26") (pin "P$3") (pinfunction "P$3_P$3") (pintype "bidirectional"))
    )
    (net (code "46") (name "X_DIR_OUT") (class "Default")
      (node (ref "J9") (pin "P$1") (pinfunction "P$1_P$1") (pintype "bidirectional"))
      (node (ref "U4") (pin "3") (pinfunction "C(3)_3") (pintype "input"))
    )
    (net (code "47") (name "X_LS") (class "Default")
      (node (ref "J10") (pin "P$4") (pinfunction "P$4_P$4") (pintype "bidirectional"))
      (node (ref "U$23") (pin "1") (pinfunction "1_1") (pintype "passive"))
      (node (ref "U$26") (pin "P$2") (pinfunction "P$2_P$2") (pintype "bidirectional"))
    )
    (net (code "48") (name "X_STEP") (class "Default")
      (node (ref "RXS1") (pin "1") (pinfunction "1_1") (pintype "passive"))
      (node (ref "U$26") (pin "P$11") (pinfunction "P$11_P$11") (pintype "bidirectional"))
    )
    (net (code "49") (name "X_STEP_OUT") (class "Default")
      (node (ref "J8") (pin "P$1") (pinfunction "P$1_P$1") (pintype "bidirectional"))
      (node (ref "U3") (pin "3") (pinfunction "C(3)_3") (pintype "input"))
    )
    (net (code "50") (name "Y_DIR") (class "Default")
      (node (ref "RYD1") (pin "1") (pinfunction "1_1") (pintype "passive"))
      (node (ref "U$26") (pin "P$5") (pinfunction "P$5_P$5") (pintype "bidirectional"))
    )
    (net (code "51") (name "Y_DIR_OUT") (class "Default")
      (node (ref "J9") (pin "P$2") (pinfunction "P$2_P$2") (pintype "bidirectional"))
      (node (ref "U6") (pin "3") (pinfunction "C(3)_3") (pintype "input"))
    )
    (net (code "52") (name "Y_LS") (class "Default")
      (node (ref "J10") (pin "P$3") (pinfunction "P$3_P$3") (pintype "bidirectional"))
      (node (ref "U$25") (pin "1") (pinfunction "1_1") (pintype "passive"))
      (node (ref "U$26") (pin "P$4") (pinfunction "P$4_P$4") (pintype "bidirectional"))
    )
    (net (code "53") (name "Y_STEP") (class "Default")
      (node (ref "RYS1") (pin "1") (pinfunction "1_1") (pintype "passive"))
      (node (ref "U$26") (pin "P$13") (pinfunction "P$13_P$13") (pintype "bidirectional"))
    )
    (net (code "54") (name "Y_STEP_OUT") (class "Default")
      (node (ref "J8") (pin "P$2") (pinfunction "P$2_P$2") (pintype "bidirectional"))
      (node (ref "U5") (pin "3") (pinfunction "C(3)_3") (pintype "input"))
    )
    (net (code "55") (name "Z_DIR") (class "Default")
      (node (ref "RZD1") (pin "1") (pinfunction "1_1") (pintype "passive"))
      (node (ref "U$26") (pin "P$1") (pinfunction "P$1_P$1") (pintype "bidirectional"))
    )
    (net (code "56") (name "Z_DIR_OUT") (class "Default")
      (node (ref "J9") (pin "P$3") (pinfunction "P$3_P$3") (pintype "bidirectional"))
      (node (ref "U2") (pin "3") (pinfunction "C(3)_3") (pintype "input"))
    )
    (net (code "57") (name "Z_LS") (class "Default")
      (node (ref "J10") (pin "P$2") (pinfunction "P$2_P$2") (pintype "bidirectional"))
      (node (ref "U$26") (pin "P$6") (pinfunction "P$6_P$6") (pintype "bidirectional"))
      (node (ref "U$27") (pin "1") (pinfunction "1_1") (pintype "passive"))
    )
    (net (code "58") (name "Z_STEP") (class "Default")
      (node (ref "RZS1") (pin "1") (pinfunction "1_1") (pintype "passive"))
      (node (ref "U$26") (pin "P$9") (pinfunction "P$9_P$9") (pintype "bidirectional"))
    )
    (net (code "59") (name "Z_STEP_OUT") (class "Default")
      (node (ref "J8") (pin "P$3") (pinfunction "P$3_P$3") (pintype "bidirectional"))
      (node (ref "U1") (pin "3") (pinfunction "C(3)_3") (pintype "input"))
    )
    (net (code "60") (name "unconnected-(J3--12V-Pad14)") (class "Default")
      (node (ref "J3") (pin "14") (pinfunction "-12V_14") (pintype "bidirectional"))
    )
    (net (code "61") (name "unconnected-(J3-12V-Pad10)") (class "Default")
      (node (ref "J3") (pin "10") (pinfunction "12V_10") (pintype "bidirectional"))
    )
    (net (code "62") (name "unconnected-(J3-12V-Pad11)") (class "Default")
      (node (ref "J3") (pin "11") (pinfunction "12V_11") (pintype "bidirectional"))
    )
    (net (code "63") (name "unconnected-(J3-NC-Pad20)") (class "Default")
      (node (ref "J3") (pin "20") (pinfunction "NC_20") (pintype "bidirectional"))
    )
  )
)
